# Trinamic.net
KiCad netlist of a schematic drawn in Altium Designer
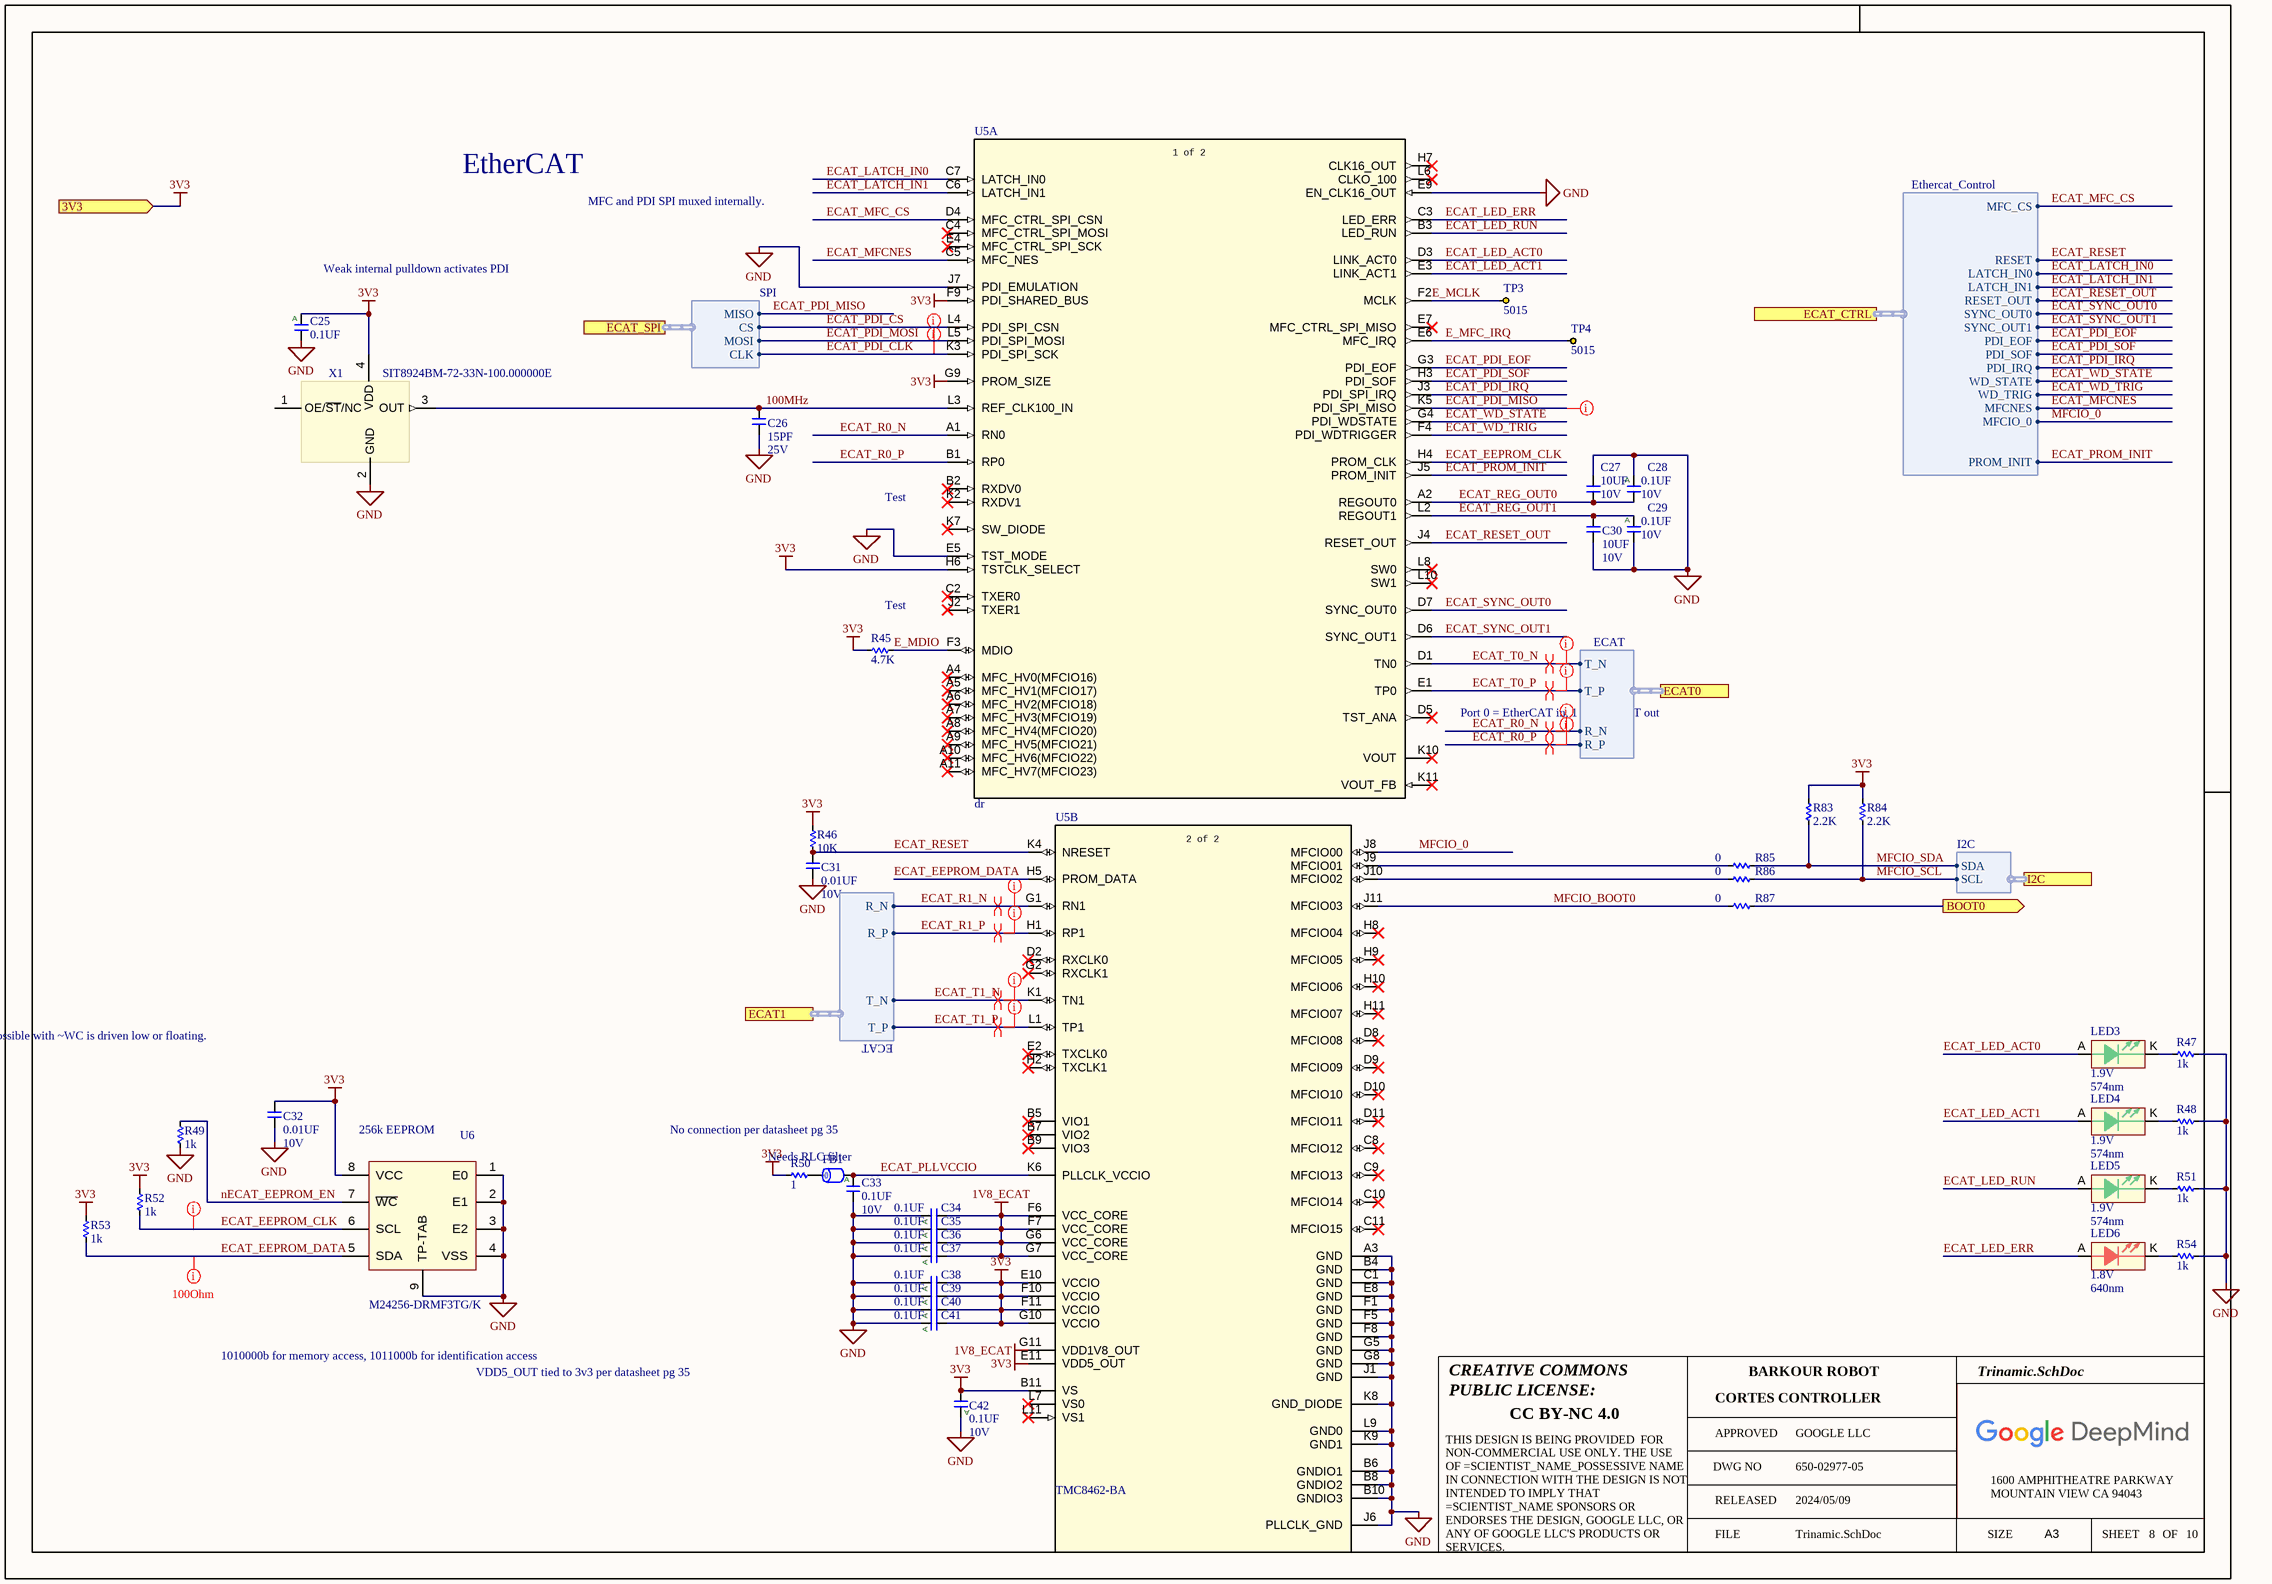
[diagram p0: Trinamic.SchDoc]

(export (version "E")
  (design (tool "Eeschema 10.0.6"))
  (components
    (comp (ref "C25")
      (value "0.1UF")
      (footprint "C0201Y")
      (description "CAP, CER, X6S, 0.1uF, 10V, 10%, 0201, AUTOGRADE")
      (fields (field (name "MFG") "MURATA") (field (name "VOLTAGE") "10V"))
      (libsource (lib "AltiumReleaseLibDB") (part "__Template_Cap_Auto"))
    )
    (comp (ref "C26")
      (value "15PF")
      (footprint "C0201")
      (description "CAP, CER, NP0, 15pF, 25V, 5%, 0201, 0.9mm T")
      (fields (field (name "MFG") "TDK") (field (name "VOLTAGE") "25V") (field (name "TOLERANCE") "5%"))
      (libsource (lib "AltiumReleaseLibDB") (part "__Template_Cap"))
    )
    (comp (ref "C27")
      (value "10UF")
      (footprint "C0402")
      (description "CAP, CER, X5R, 10uF, 10V, 20%, 0402, 0.7mm T")
      (fields (field (name "MFG") "SAMSUNG") (field (name "VOLTAGE") "10V") (field (name "TOLERANCE") "20%"))
      (libsource (lib "AltiumReleaseLibDB") (part "__Template_Cap"))
    )
    (comp (ref "C28")
      (value "0.1UF")
      (footprint "C0201Y")
      (description "CAP, CER, X6S, 0.1uF, 10V, 10%, 0201, AUTOGRADE")
      (fields (field (name "MFG") "MURATA") (field (name "VOLTAGE") "10V") (field (name "TOLERANCE") "10%"))
      (libsource (lib "AltiumReleaseLibDB") (part "__Template_Cap_Auto"))
    )
    (comp (ref "C29")
      (value "0.1UF")
      (footprint "C0201Y")
      (description "CAP, CER, X6S, 0.1uF, 10V, 10%, 0201, AUTOGRADE")
      (fields (field (name "MFG") "MURATA") (field (name "VOLTAGE") "10V") (field (name "TOLERANCE") "10%"))
      (libsource (lib "AltiumReleaseLibDB") (part "__Template_Cap_Auto"))
    )
    (comp (ref "C30")
      (value "10UF")
      (footprint "C0402")
      (description "CAP, CER, X5R, 10uF, 10V, 20%, 0402, 0.7mm T")
      (fields (field (name "MFG") "SAMSUNG") (field (name "VOLTAGE") "10V") (field (name "TOLERANCE") "20%"))
      (libsource (lib "AltiumReleaseLibDB") (part "__Template_Cap"))
    )
    (comp (ref "C31")
      (value "0.01UF")
      (footprint "C0201Y")
      (description "CAP, CER, X7R, 0.01uF, 10V, 10%, AUTO GRADE, 0201, 0.33mm T")
      (fields (field (name "MFG") "MURATA") (field (name "VOLTAGE") "10V") (field (name "TOLERANCE") "10%"))
      (libsource (lib "AltiumReleaseLibDB") (part "__Template_Cap"))
    )
    (comp (ref "C32")
      (value "0.01UF")
      (footprint "C0201Y")
      (description "CAP, CER, X7R, 0.01uF, 10V, 10%, AUTO GRADE, 0201, 0.33mm T")
      (fields (field (name "MFG") "MURATA") (field (name "VOLTAGE") "10V") (field (name "TOLERANCE") "10%"))
      (libsource (lib "AltiumReleaseLibDB") (part "__Template_Cap"))
    )
    (comp (ref "C33")
      (value "0.1UF")
      (footprint "C0201Y")
      (description "CAP, CER, X6S, 0.1uF, 10V, 10%, 0201, AUTOGRADE")
      (fields (field (name "MFG") "MURATA") (field (name "VOLTAGE") "10V") (field (name "TOLERANCE") "10%"))
      (libsource (lib "AltiumReleaseLibDB") (part "__Template_Cap_Auto"))
    )
    (comp (ref "C34")
      (value "0.1UF")
      (footprint "C0201Y")
      (description "CAP, CER, X6S, 0.1uF, 10V, 10%, 0201, AUTOGRADE")
      (fields (field (name "MFG") "MURATA") (field (name "VOLTAGE") "10V"))
      (libsource (lib "AltiumReleaseLibDB") (part "__Template_Cap_Auto"))
    )
    (comp (ref "C35")
      (value "0.1UF")
      (footprint "C0201Y")
      (description "CAP, CER, X6S, 0.1uF, 10V, 10%, 0201, AUTOGRADE")
      (fields (field (name "MFG") "MURATA") (field (name "VOLTAGE") "10V"))
      (libsource (lib "AltiumReleaseLibDB") (part "__Template_Cap_Auto"))
    )
    (comp (ref "C36")
      (value "0.1UF")
      (footprint "C0201Y")
      (description "CAP, CER, X6S, 0.1uF, 10V, 10%, 0201, AUTOGRADE")
      (fields (field (name "MFG") "MURATA") (field (name "VOLTAGE") "10V"))
      (libsource (lib "AltiumReleaseLibDB") (part "__Template_Cap_Auto"))
    )
    (comp (ref "C37")
      (value "0.1UF")
      (footprint "C0201Y")
      (description "CAP, CER, X6S, 0.1uF, 10V, 10%, 0201, AUTOGRADE")
      (fields (field (name "MFG") "MURATA") (field (name "VOLTAGE") "10V"))
      (libsource (lib "AltiumReleaseLibDB") (part "__Template_Cap_Auto"))
    )
    (comp (ref "C38")
      (value "0.1UF")
      (footprint "C0201Y")
      (description "CAP, CER, X6S, 0.1uF, 10V, 10%, 0201, AUTOGRADE")
      (fields (field (name "MFG") "MURATA") (field (name "VOLTAGE") "10V"))
      (libsource (lib "AltiumReleaseLibDB") (part "__Template_Cap_Auto"))
    )
    (comp (ref "C39")
      (value "0.1UF")
      (footprint "C0201Y")
      (description "CAP, CER, X6S, 0.1uF, 10V, 10%, 0201, AUTOGRADE")
      (fields (field (name "MFG") "MURATA") (field (name "VOLTAGE") "10V"))
      (libsource (lib "AltiumReleaseLibDB") (part "__Template_Cap_Auto"))
    )
    (comp (ref "C40")
      (value "0.1UF")
      (footprint "C0201Y")
      (description "CAP, CER, X6S, 0.1uF, 10V, 10%, 0201, AUTOGRADE")
      (fields (field (name "MFG") "MURATA") (field (name "VOLTAGE") "10V"))
      (libsource (lib "AltiumReleaseLibDB") (part "__Template_Cap_Auto"))
    )
    (comp (ref "C41")
      (value "0.1UF")
      (footprint "C0201Y")
      (description "CAP, CER, X6S, 0.1uF, 10V, 10%, 0201, AUTOGRADE")
      (fields (field (name "MFG") "MURATA") (field (name "VOLTAGE") "10V"))
      (libsource (lib "AltiumReleaseLibDB") (part "__Template_Cap_Auto"))
    )
    (comp (ref "C42")
      (value "0.1UF")
      (footprint "C0201Y")
      (description "CAP, CER, X6S, 0.1uF, 10V, 10%, 0201, AUTOGRADE")
      (fields (field (name "MFG") "MURATA") (field (name "VOLTAGE") "10V") (field (name "TOLERANCE") "10%"))
      (libsource (lib "AltiumReleaseLibDB") (part "__Template_Cap_Auto"))
    )
    (comp (ref "FB1")
      (value "__Template_Ferrite_Bead")
      (footprint "L0201_H0.33MM")
      (description "FERRITE, BEAD, 600OHMS @100MHZ, 25%, 250mA, 900 mOHM DCR, 0201")
      (fields (field (name "MFG") "Murata Electronics North America"))
      (libsource (lib "AltiumReleaseLibDB") (part "__Template_Ferrite_Bead"))
    )
    (comp (ref "LED3")
      (value "__Template_LED_GREEN_AK")
      (footprint "LED_APHHS1005LCGCK")
      (description "LED, GREEN, 574nm, 2mA, CLEAR, 0402")
      (fields
        (field (name "MFG") "Kingbright")
        (field (name "VOLTAGE – FORWARD (VF) (MAX) @ IF") "1.9V")
        (field (name "COLOR / WAVELENGTH") "574nm")
      )
      (libsource (lib "AltiumReleaseLibDB") (part "__Template_LED_GREEN_AK"))
    )
    (comp (ref "LED4")
      (value "__Template_LED_GREEN_AK")
      (footprint "LED_APHHS1005LCGCK")
      (description "LED, GREEN, 574nm, 2mA, CLEAR, 0402")
      (fields
        (field (name "MFG") "Kingbright")
        (field (name "VOLTAGE – FORWARD (VF) (MAX) @ IF") "1.9V")
        (field (name "COLOR / WAVELENGTH") "574nm")
      )
      (libsource (lib "AltiumReleaseLibDB") (part "__Template_LED_GREEN_AK"))
    )
    (comp (ref "LED5")
      (value "__Template_LED_GREEN_AK")
      (footprint "LED_APHHS1005LCGCK")
      (description "LED, GREEN, 574nm, 2mA, CLEAR, 0402")
      (fields
        (field (name "MFG") "Kingbright")
        (field (name "VOLTAGE – FORWARD (VF) (MAX) @ IF") "1.9V")
        (field (name "COLOR / WAVELENGTH") "574nm")
      )
      (libsource (lib "AltiumReleaseLibDB") (part "__Template_LED_GREEN_AK"))
    )
    (comp (ref "LED6")
      (value "__Template_LED_RED_AK")
      (footprint "LED_APHHS1005LCGCK")
      (description "LED, RED, 640NM, 2mA, CLEAR, 0402")
      (fields
        (field (name "MFG") "Kingbright")
        (field (name "VOLTAGE – FORWARD (VF) (MAX) @ IF") "1.8V")
        (field (name "COLOR / WAVELENGTH") "640nm")
      )
      (libsource (lib "AltiumReleaseLibDB") (part "__Template_LED_RED_AK"))
    )
    (comp (ref "R45")
      (value "4.7K")
      (footprint "R0201_H0.26MM")
      (description "RES, 4.7K, 1%, 1/20W, 0201, AUTOGRADE")
      (fields (field (name "MFG") "Panasonic Electronic Components") (field (name "POWER") "0.05W, 1/20W"))
      (libsource (lib "AltiumReleaseLibDB") (part "__Template_Resistor"))
    )
    (comp (ref "R46")
      (value "10K")
      (footprint "R0201_H0.26MM")
      (description "RES, 10K, 1%, 1/20W, 0201, AUTOGRADE")
      (fields (field (name "MFG") "PANASONIC") (field (name "POWER") "1/20W"))
      (libsource (lib "AltiumReleaseLibDB") (part "__Template_Resistor"))
    )
    (comp (ref "R47")
      (value "1k")
      (footprint "R0201_H0.26MM")
      (description "RES, 1K, 1%, 1/20W, 0201, AUTOGRADE")
      (fields (field (name "MFG") "Bourns Inc.") (field (name "POWER") "0.05W, 1/20W"))
      (libsource (lib "AltiumReleaseLibDB") (part "__Template_Resistor"))
    )
    (comp (ref "R48")
      (value "1k")
      (footprint "R0201_H0.26MM")
      (description "RES, 1K, 1%, 1/20W, 0201, AUTOGRADE")
      (fields (field (name "MFG") "Bourns Inc.") (field (name "POWER") "0.05W, 1/20W"))
      (libsource (lib "AltiumReleaseLibDB") (part "__Template_Resistor"))
    )
    (comp (ref "R49")
      (value "1k")
      (footprint "R0201_H0.26MM")
      (description "RES, 1K, 1%, 1/20W, 0201, AUTOGRADE")
      (fields (field (name "MFG") "Bourns Inc.") (field (name "POWER") "0.05W, 1/20W"))
      (libsource (lib "AltiumReleaseLibDB") (part "__Template_Resistor"))
    )
    (comp (ref "R50")
      (value "1")
      (footprint "R0201")
      (description "RES, 1.0, 5%, 1/20W, 0201")
      (fields (field (name "MFG") "PANASONIC") (field (name "POWER") "1/20W"))
      (libsource (lib "AltiumReleaseLibDB") (part "__Template_Resistor"))
    )
    (comp (ref "R51")
      (value "1k")
      (footprint "R0201_H0.26MM")
      (description "RES, 1K, 1%, 1/20W, 0201, AUTOGRADE")
      (fields (field (name "MFG") "Bourns Inc.") (field (name "POWER") "0.05W, 1/20W"))
      (libsource (lib "AltiumReleaseLibDB") (part "__Template_Resistor"))
    )
    (comp (ref "R52")
      (value "1k")
      (footprint "R0201_H0.26MM")
      (description "RES, 1K, 1%, 1/20W, 0201, AUTOGRADE")
      (fields (field (name "MFG") "Bourns Inc.") (field (name "POWER") "0.05W, 1/20W"))
      (libsource (lib "AltiumReleaseLibDB") (part "__Template_Resistor"))
    )
    (comp (ref "R53")
      (value "1k")
      (footprint "R0201_H0.26MM")
      (description "RES, 1K, 1%, 1/20W, 0201, AUTOGRADE")
      (fields (field (name "MFG") "Bourns Inc.") (field (name "POWER") "0.05W, 1/20W"))
      (libsource (lib "AltiumReleaseLibDB") (part "__Template_Resistor"))
    )
    (comp (ref "R54")
      (value "1k")
      (footprint "R0201_H0.26MM")
      (description "RES, 1K, 1%, 1/20W, 0201, AUTOGRADE")
      (fields (field (name "MFG") "Bourns Inc.") (field (name "POWER") "0.05W, 1/20W"))
      (libsource (lib "AltiumReleaseLibDB") (part "__Template_Resistor"))
    )
    (comp (ref "R83")
      (value "2.2K")
      (footprint "R0201")
      (description "Resistor, 2.20K Ohms, 0201, 0.05W, ±1%")
      (fields (field (name "MFG") "PANASONIC") (field (name "POWER") "1/20W"))
      (libsource (lib "AltiumReleaseLibDB") (part "__Template_Resistor"))
    )
    (comp (ref "R84")
      (value "2.2K")
      (footprint "R0201")
      (description "Resistor, 2.20K Ohms, 0201, 0.05W, ±1%")
      (fields (field (name "MFG") "PANASONIC") (field (name "POWER") "1/20W"))
      (libsource (lib "AltiumReleaseLibDB") (part "__Template_Resistor"))
    )
    (comp (ref "R85")
      (value "0")
      (footprint "R0402")
      (description "RES, 0, JUMPER, 1/16W, 0402")
      (fields (field (name "MFG") "YAGEO") (field (name "POWER") "1/16W"))
      (libsource (lib "AltiumReleaseLibDB") (part "__Template_Resistor"))
    )
    (comp (ref "R86")
      (value "0")
      (footprint "R0402")
      (description "RES, 0, JUMPER, 1/16W, 0402")
      (fields (field (name "MFG") "YAGEO") (field (name "POWER") "1/16W"))
      (libsource (lib "AltiumReleaseLibDB") (part "__Template_Resistor"))
    )
    (comp (ref "R87")
      (value "0")
      (footprint "R0402")
      (description "RES, 0, JUMPER, 1/16W, 0402")
      (fields (field (name "MFG") "YAGEO") (field (name "POWER") "1/16W"))
      (libsource (lib "AltiumReleaseLibDB") (part "__Template_Resistor"))
    )
    (comp (ref "TP3")
      (value "KEYSTONE5015_NOSILK")
      (footprint "KEYSTONE_5015_NS")
      (description "HW, TEST POINT, NO SILKSCREEN, PC MINIATURE, 0.25mm T, 1.52mm HEIGHT, SILVER PLATING, SMT")
      (fields (field (name "MFG") "Keystone Electronics Corp.") (field (name "MFG P/N") "5015"))
      (libsource (lib "AltiumReleaseLibDB") (part "TEST_KEYSTONE5015_NOSILK"))
    )
    (comp (ref "TP4")
      (value "KEYSTONE5015_NOSILK")
      (footprint "KEYSTONE_5015_NS")
      (description "HW, TEST POINT, NO SILKSCREEN, PC MINIATURE, 0.25mm T, 1.52mm HEIGHT, SILVER PLATING, SMT")
      (fields (field (name "MFG") "Keystone Electronics Corp.") (field (name "MFG P/N") "5015"))
      (libsource (lib "AltiumReleaseLibDB") (part "TEST_KEYSTONE5015_NOSILK"))
    )
    (comp (ref "U5")
      (value "PROCESSOR_TRINAMIC_TMC8462-BA")
      (footprint "BGA121C75P11X11_900X900X145")
      (description "IC, CONTROLLER, TMC8462, ETHERNET, 100Mb, SPI, PWM O/P, 100mA, BGA-121")
      (fields (field (name "MFG") "Trinamic Motion Control GmbH") (field (name "MFG P/N") "dr"))
      (libsource (lib "AltiumReleaseLibDB") (part "PROCESSOR_TRINAMIC_TMC8462-BA"))
    )
    (comp (ref "U6")
      (value "EEPROM_M24256-DRMF3TG/K")
      (footprint "8WFDFN300X200X80-8-TP")
      (description "IC, MEMORY, M24256, EEPROM, 256Kb, I2C, 1MHz, MLP-8, AUTOGRADE")
      (fields (field (name "MFG") "STMicroelectronics") (field (name "MFG P/N") "M24256-DRMF3TG/K"))
      (libsource (lib "AltiumReleaseLibDB") (part "EEPROM_M24256-DRMF3TG/K"))
    )
    (comp (ref "X1")
      (value "XTAL_SIT8924BM-72-33N-100.000000")
      (footprint "XTAL_SIT8924BM-72-33N-100.000000")
      (description "OSC, MEMS, XO, 100MHZ, +/-25PPM STAB, LVCMOS, 3.3V, SMD-4, AUTOGRADE")
      (fields (field (name "MFG") "SiTIME") (field (name "MFG P/N") "SIT8924BM-72-33N-100.000000E"))
      (libsource (lib "AltiumReleaseLibDB") (part "XTAL_SIT8924BM-72-33N-100.000000"))
    )
  )
  (nets
    (net (code "5") (name "/100MHz") (class "Default")
      (node (ref "C26") (pin "1") (pintype "passive"))
      (node (ref "U5") (pin "L3") (pinfunction "REF_CLK100_IN_L3") (pintype "input"))
      (node (ref "X1") (pin "3") (pinfunction "OUT_3") (pintype "output"))
    )
    (net (code "6") (name "/BOOT0") (class "Default") (node (ref "R87") (pin "2") (pintype "passive")))
    (net (code "7") (name "/ECAT_EEPROM_CLK") (class "Default")
      (node (ref "R52") (pin "1") (pintype "passive"))
      (node (ref "U5") (pin "H4") (pinfunction "PROM_CLK_H4") (pintype "output"))
      (node (ref "U6") (pin "6") (pinfunction "SCL_6") (pintype "passive"))
    )
    (net (code "8") (name "/ECAT_EEPROM_DATA") (class "Default")
      (node (ref "R53") (pin "1") (pintype "passive"))
      (node (ref "U5") (pin "H5") (pinfunction "PROM_DATA_H5") (pintype "bidirectional"))
      (node (ref "U6") (pin "5") (pinfunction "SDA_5") (pintype "passive"))
    )
    (net (code "9") (name "/ECAT_LATCH_IN0") (class "Default")
      (node (ref "U5") (pin "C7") (pinfunction "LATCH_IN0_C7") (pintype "input"))
    )
    (net (code "10") (name "/ECAT_LATCH_IN1") (class "Default")
      (node (ref "U5") (pin "C6") (pinfunction "LATCH_IN1_C6") (pintype "input"))
    )
    (net (code "11") (name "/ECAT_LED_ACT0") (class "Default")
      (node (ref "LED3") (pin "A") (pinfunction "A_A") (pintype "passive"))
      (node (ref "U5") (pin "D3") (pinfunction "LINK_ACT0_D3") (pintype "output"))
    )
    (net (code "12") (name "/ECAT_LED_ACT1") (class "Default")
      (node (ref "LED4") (pin "A") (pinfunction "A_A") (pintype "passive"))
      (node (ref "U5") (pin "E3") (pinfunction "LINK_ACT1_E3") (pintype "output"))
    )
    (net (code "13") (name "/ECAT_LED_ERR") (class "Default")
      (node (ref "LED6") (pin "A") (pinfunction "A_A") (pintype "passive"))
      (node (ref "U5") (pin "C3") (pinfunction "LED_ERR_C3") (pintype "output"))
    )
    (net (code "14") (name "/ECAT_LED_RUN") (class "Default")
      (node (ref "LED5") (pin "A") (pinfunction "A_A") (pintype "passive"))
      (node (ref "U5") (pin "B3") (pinfunction "LED_RUN_B3") (pintype "output"))
    )
    (net (code "15") (name "/ECAT_MFCNES") (class "Default")
      (node (ref "U5") (pin "C5") (pinfunction "MFC_NES_C5") (pintype "input"))
    )
    (net (code "16") (name "/ECAT_MFC_CS") (class "Default")
      (node (ref "U5") (pin "D4") (pinfunction "MFC_CTRL_SPI_CSN_D4") (pintype "input"))
    )
    (net (code "17") (name "/ECAT_PDI_CLK") (class "Default")
      (node (ref "U5") (pin "K3") (pinfunction "PDI_SPI_SCK_K3") (pintype "input"))
    )
    (net (code "18") (name "/ECAT_PDI_CS") (class "Default")
      (node (ref "U5") (pin "L4") (pinfunction "PDI_SPI_CSN_L4") (pintype "input"))
    )
    (net (code "19") (name "/ECAT_PDI_EOF") (class "Default")
      (node (ref "U5") (pin "G3") (pinfunction "PDI_EOF_G3") (pintype "output"))
    )
    (net (code "20") (name "/ECAT_PDI_IRQ") (class "Default")
      (node (ref "U5") (pin "J3") (pinfunction "PDI_SPI_IRQ_J3") (pintype "output"))
    )
    (net (code "21") (name "/ECAT_PDI_MISO") (class "Default")
      (node (ref "U5") (pin "K5") (pinfunction "PDI_SPI_MISO_K5") (pintype "output"))
    )
    (net (code "22") (name "/ECAT_PDI_MOSI") (class "Default")
      (node (ref "U5") (pin "L5") (pinfunction "PDI_SPI_MOSI_L5") (pintype "input"))
    )
    (net (code "23") (name "/ECAT_PDI_SOF") (class "Default")
      (node (ref "U5") (pin "H3") (pinfunction "PDI_SOF_H3") (pintype "output"))
    )
    (net (code "24") (name "/ECAT_PLLVCCIO") (class "Default")
      (node (ref "C33") (pin "1") (pintype "passive"))
      (node (ref "FB1") (pin "2") (pinfunction "2_2") (pintype "passive"))
      (node (ref "U5") (pin "K6") (pinfunction "PLLCLK_VCCIO_K6") (pintype "power_in"))
    )
    (net (code "25") (name "/ECAT_PROM_INIT") (class "Default")
      (node (ref "U5") (pin "J5") (pinfunction "PROM_INIT_J5") (pintype "output"))
    )
    (net (code "26") (name "/ECAT_R0_N") (class "Default")
      (node (ref "U5") (pin "A1") (pinfunction "RN0_A1") (pintype "input"))
    )
    (net (code "27") (name "/ECAT_R0_P") (class "Default")
      (node (ref "U5") (pin "B1") (pinfunction "RP0_B1") (pintype "input"))
    )
    (net (code "28") (name "/ECAT_R1_N") (class "Default")
      (node (ref "U5") (pin "G1") (pinfunction "RN1_G1") (pintype "bidirectional"))
    )
    (net (code "29") (name "/ECAT_R1_P") (class "Default")
      (node (ref "U5") (pin "H1") (pinfunction "RP1_H1") (pintype "bidirectional"))
    )
    (net (code "30") (name "/ECAT_REG_OUT0") (class "Default")
      (node (ref "C27") (pin "2") (pintype "passive"))
      (node (ref "C28") (pin "2") (pintype "passive"))
      (node (ref "U5") (pin "A2") (pinfunction "REGOUT0_A2") (pintype "output"))
    )
    (net (code "31") (name "/ECAT_REG_OUT1") (class "Default")
      (node (ref "C29") (pin "1") (pintype "passive"))
      (node (ref "C30") (pin "1") (pintype "passive"))
      (node (ref "U5") (pin "L2") (pinfunction "REGOUT1_L2") (pintype "output"))
    )
    (net (code "32") (name "/ECAT_RESET") (class "Default")
      (node (ref "C31") (pin "1") (pintype "passive"))
      (node (ref "R46") (pin "1") (pintype "passive"))
      (node (ref "U5") (pin "K4") (pinfunction "NRESET_K4") (pintype "bidirectional"))
    )
    (net (code "33") (name "/ECAT_RESET_OUT") (class "Default")
      (node (ref "U5") (pin "J4") (pinfunction "RESET_OUT_J4") (pintype "output"))
    )
    (net (code "34") (name "/ECAT_SYNC_OUT0") (class "Default")
      (node (ref "U5") (pin "D7") (pinfunction "SYNC_OUT0_D7") (pintype "output"))
    )
    (net (code "35") (name "/ECAT_SYNC_OUT1") (class "Default")
      (node (ref "U5") (pin "D6") (pinfunction "SYNC_OUT1_D6") (pintype "output"))
    )
    (net (code "36") (name "/ECAT_T0_N") (class "Default")
      (node (ref "U5") (pin "D1") (pinfunction "TN0_D1") (pintype "output"))
    )
    (net (code "37") (name "/ECAT_T0_P") (class "Default")
      (node (ref "U5") (pin "E1") (pinfunction "TP0_E1") (pintype "output"))
    )
    (net (code "38") (name "/ECAT_T1_N") (class "Default")
      (node (ref "U5") (pin "K1") (pinfunction "TN1_K1") (pintype "bidirectional"))
    )
    (net (code "39") (name "/ECAT_T1_P") (class "Default")
      (node (ref "U5") (pin "L1") (pinfunction "TP1_L1") (pintype "bidirectional"))
    )
    (net (code "40") (name "/ECAT_WD_STATE") (class "Default")
      (node (ref "U5") (pin "G4") (pinfunction "PDI_WDSTATE_G4") (pintype "output"))
    )
    (net (code "41") (name "/ECAT_WD_TRIG") (class "Default")
      (node (ref "U5") (pin "F4") (pinfunction "PDI_WDTRIGGER_F4") (pintype "output"))
    )
    (net (code "42") (name "/E_MCLK") (class "Default")
      (node (ref "TP3") (pin "1") (pintype "passive"))
      (node (ref "U5") (pin "F2") (pinfunction "MCLK_F2") (pintype "output"))
    )
    (net (code "43") (name "/E_MDIO") (class "Default")
      (node (ref "R45") (pin "1") (pintype "passive"))
      (node (ref "U5") (pin "F3") (pinfunction "MDIO_F3") (pintype "bidirectional"))
    )
    (net (code "44") (name "/E_MFC_IRQ") (class "Default")
      (node (ref "TP4") (pin "1") (pintype "passive"))
      (node (ref "U5") (pin "E6") (pinfunction "MFC_IRQ_E6") (pintype "output"))
    )
    (net (code "45") (name "/MFCIO_0") (class "Default")
      (node (ref "U5") (pin "J8") (pinfunction "MFCIO00_J8") (pintype "bidirectional"))
    )
    (net (code "46") (name "/MFCIO_BOOT0") (class "Default")
      (node (ref "R87") (pin "1") (pintype "passive"))
      (node (ref "U5") (pin "J11") (pinfunction "MFCIO03_J11") (pintype "bidirectional"))
    )
    (net (code "47") (name "/MFCIO_SCL") (class "Default")
      (node (ref "R84") (pin "1") (pintype "passive"))
      (node (ref "R86") (pin "2") (pintype "passive"))
    )
    (net (code "48") (name "/MFCIO_SDA") (class "Default")
      (node (ref "R83") (pin "1") (pintype "passive"))
      (node (ref "R85") (pin "2") (pintype "passive"))
    )
    (net (code "49") (name "/nECAT_EEPROM_EN") (class "Default")
      (node (ref "R49") (pin "2") (pintype "passive"))
      (node (ref "U6") (pin "7") (pinfunction "~{WC}_7") (pintype "passive"))
    )
    (net (code "54") (name "1V8_ECAT") (class "Default")
      (node (ref "C34") (pin "2") (pintype "passive"))
      (node (ref "C35") (pin "2") (pintype "passive"))
      (node (ref "C36") (pin "2") (pintype "passive"))
      (node (ref "C37") (pin "2") (pintype "passive"))
      (node (ref "U5") (pin "F6") (pinfunction "VCC_CORE_F6") (pintype "power_in"))
      (node (ref "U5") (pin "F7") (pinfunction "VCC_CORE_F7") (pintype "power_in"))
      (node (ref "U5") (pin "G11") (pinfunction "VDD1V8_OUT_G11") (pintype "power_in"))
      (node (ref "U5") (pin "G6") (pinfunction "VCC_CORE_G6") (pintype "power_in"))
      (node (ref "U5") (pin "G7") (pinfunction "VCC_CORE_G7") (pintype "power_in"))
    )
    (net (code "55") (name "3V3") (class "Default")
      (node (ref "C25") (pin "1") (pintype "passive"))
      (node (ref "C32") (pin "1") (pintype "passive"))
      (node (ref "C38") (pin "2") (pintype "passive"))
      (node (ref "C39") (pin "2") (pintype "passive"))
      (node (ref "C40") (pin "2") (pintype "passive"))
      (node (ref "C41") (pin "2") (pintype "passive"))
      (node (ref "C42") (pin "2") (pintype "passive"))
      (node (ref "R45") (pin "2") (pintype "passive"))
      (node (ref "R46") (pin "2") (pintype "passive"))
      (node (ref "R50") (pin "1") (pintype "passive"))
      (node (ref "R52") (pin "2") (pintype "passive"))
      (node (ref "R53") (pin "2") (pintype "passive"))
      (node (ref "R83") (pin "2") (pintype "passive"))
      (node (ref "R84") (pin "2") (pintype "passive"))
      (node (ref "U5") (pin "B11") (pinfunction "VS_B11") (pintype "power_in"))
      (node (ref "U5") (pin "E10") (pinfunction "VCCIO_E10") (pintype "power_in"))
      (node (ref "U5") (pin "E11") (pinfunction "VDD5_OUT_E11") (pintype "power_in"))
      (node (ref "U5") (pin "F10") (pinfunction "VCCIO_F10") (pintype "power_in"))
      (node (ref "U5") (pin "F11") (pinfunction "VCCIO_F11") (pintype "power_in"))
      (node (ref "U5") (pin "F9") (pinfunction "PDI_SHARED_BUS_F9") (pintype "input"))
      (node (ref "U5") (pin "G10") (pinfunction "VCCIO_G10") (pintype "power_in"))
      (node (ref "U5") (pin "G9") (pinfunction "PROM_SIZE_G9") (pintype "input"))
      (node (ref "U5") (pin "H6") (pinfunction "TSTCLK_SELECT_H6") (pintype "input"))
      (node (ref "U6") (pin "8") (pinfunction "VCC_8") (pintype "passive"))
      (node (ref "X1") (pin "4") (pinfunction "VDD_4") (pintype "power_in"))
    )
    (net (code "56") (name "GND") (class "Default")
      (node (ref "C25") (pin "2") (pintype "passive"))
      (node (ref "C26") (pin "2") (pintype "passive"))
      (node (ref "C27") (pin "1") (pintype "passive"))
      (node (ref "C28") (pin "1") (pintype "passive"))
      (node (ref "C29") (pin "2") (pintype "passive"))
      (node (ref "C30") (pin "2") (pintype "passive"))
      (node (ref "C31") (pin "2") (pintype "passive"))
      (node (ref "C32") (pin "2") (pintype "passive"))
      (node (ref "C33") (pin "2") (pintype "passive"))
      (node (ref "C34") (pin "1") (pintype "passive"))
      (node (ref "C35") (pin "1") (pintype "passive"))
      (node (ref "C36") (pin "1") (pintype "passive"))
      (node (ref "C37") (pin "1") (pintype "passive"))
      (node (ref "C38") (pin "1") (pintype "passive"))
      (node (ref "C39") (pin "1") (pintype "passive"))
      (node (ref "C40") (pin "1") (pintype "passive"))
      (node (ref "C41") (pin "1") (pintype "passive"))
      (node (ref "C42") (pin "1") (pintype "passive"))
      (node (ref "R47") (pin "1") (pintype "passive"))
      (node (ref "R48") (pin "1") (pintype "passive"))
      (node (ref "R49") (pin "1") (pintype "passive"))
      (node (ref "R51") (pin "1") (pintype "passive"))
      (node (ref "R54") (pin "1") (pintype "passive"))
      (node (ref "U5") (pin "A3") (pinfunction "GND_A3") (pintype "power_in"))
      (node (ref "U5") (pin "B10") (pinfunction "GNDIO3_B10") (pintype "power_in"))
      (node (ref "U5") (pin "B4") (pinfunction "GND_B4") (pintype "power_in"))
      (node (ref "U5") (pin "B6") (pinfunction "GNDIO1_B6") (pintype "power_in"))
      (node (ref "U5") (pin "B8") (pinfunction "GNDIO2_B8") (pintype "power_in"))
      (node (ref "U5") (pin "C1") (pinfunction "GND_C1") (pintype "power_in"))
      (node (ref "U5") (pin "E5") (pinfunction "TST_MODE_E5") (pintype "input"))
      (node (ref "U5") (pin "E8") (pinfunction "GND_E8") (pintype "power_in"))
      (node (ref "U5") (pin "E9") (pinfunction "EN_CLK16_OUT_E9") (pintype "input"))
      (node (ref "U5") (pin "F1") (pinfunction "GND_F1") (pintype "power_in"))
      (node (ref "U5") (pin "F5") (pinfunction "GND_F5") (pintype "power_in"))
      (node (ref "U5") (pin "F8") (pinfunction "GND_F8") (pintype "power_in"))
      (node (ref "U5") (pin "G5") (pinfunction "GND_G5") (pintype "power_in"))
      (node (ref "U5") (pin "G8") (pinfunction "GND_G8") (pintype "power_in"))
      (node (ref "U5") (pin "J1") (pinfunction "GND_J1") (pintype "power_in"))
      (node (ref "U5") (pin "J6") (pinfunction "PLLCLK_GND_J6") (pintype "power_in"))
      (node (ref "U5") (pin "J7") (pinfunction "PDI_EMULATION_J7") (pintype "input"))
      (node (ref "U5") (pin "K8") (pinfunction "GND_DIODE_K8") (pintype "power_in"))
      (node (ref "U5") (pin "K9") (pinfunction "GND1_K9") (pintype "power_in"))
      (node (ref "U5") (pin "L9") (pinfunction "GND0_L9") (pintype "power_in"))
      (node (ref "U6") (pin "1") (pinfunction "E0_1") (pintype "passive"))
      (node (ref "U6") (pin "2") (pinfunction "E1_2") (pintype "passive"))
      (node (ref "U6") (pin "3") (pinfunction "E2_3") (pintype "passive"))
      (node (ref "U6") (pin "4") (pinfunction "VSS_4") (pintype "passive"))
      (node (ref "U6") (pin "9") (pinfunction "TP-TAB_9") (pintype "power_in"))
      (node (ref "X1") (pin "2") (pinfunction "GND_2") (pintype "power_in"))
    )
    (net (code "57") (name "Net-(FB1-Pad1)") (class "Default")
      (node (ref "FB1") (pin "1") (pinfunction "1_1") (pintype "passive"))
      (node (ref "R50") (pin "2") (pintype "passive"))
    )
    (net (code "58") (name "Net-(LED3-PadK)") (class "Default")
      (node (ref "LED3") (pin "K") (pinfunction "K_K") (pintype "passive"))
      (node (ref "R47") (pin "2") (pintype "passive"))
    )
    (net (code "59") (name "Net-(LED4-PadK)") (class "Default")
      (node (ref "LED4") (pin "K") (pinfunction "K_K") (pintype "passive"))
      (node (ref "R48") (pin "2") (pintype "passive"))
    )
    (net (code "60") (name "Net-(LED5-PadK)") (class "Default")
      (node (ref "LED5") (pin "K") (pinfunction "K_K") (pintype "passive"))
      (node (ref "R51") (pin "2") (pintype "passive"))
    )
    (net (code "61") (name "Net-(LED6-PadK)") (class "Default")
      (node (ref "LED6") (pin "K") (pinfunction "K_K") (pintype "passive"))
      (node (ref "R54") (pin "2") (pintype "passive"))
    )
    (net (code "62") (name "Net-(U5B-MFCIO01)") (class "Default")
      (node (ref "R85") (pin "1") (pintype "passive"))
      (node (ref "U5") (pin "J9") (pinfunction "MFCIO01_J9") (pintype "bidirectional"))
    )
    (net (code "63") (name "Net-(U5B-MFCIO02)") (class "Default")
      (node (ref "R86") (pin "1") (pintype "passive"))
      (node (ref "U5") (pin "J10") (pinfunction "MFCIO02_J10") (pintype "bidirectional"))
    )
    (net (code "64") (name "unconnected-(U5A-CLK16_OUT-PadH7)") (class "Default")
      (node (ref "U5") (pin "H7") (pinfunction "CLK16_OUT_H7") (pintype "output+no_connect"))
    )
    (net (code "65") (name "unconnected-(U5A-CLKO_100-PadL6)") (class "Default")
      (node (ref "U5") (pin "L6") (pinfunction "CLKO_100_L6") (pintype "output+no_connect"))
    )
    (net (code "66") (name "unconnected-(U5A-MFC_CTRL_SPI_MISO-PadE7)") (class "Default")
      (node (ref "U5") (pin "E7") (pinfunction "MFC_CTRL_SPI_MISO_E7") (pintype "output+no_connect"))
    )
    (net (code "67") (name "unconnected-(U5A-MFC_CTRL_SPI_MOSI-PadC4)") (class "Default")
      (node (ref "U5") (pin "C4") (pinfunction "MFC_CTRL_SPI_MOSI_C4") (pintype "input+no_connect"))
    )
    (net (code "68") (name "unconnected-(U5A-MFC_CTRL_SPI_SCK-PadE4)") (class "Default")
      (node (ref "U5") (pin "E4") (pinfunction "MFC_CTRL_SPI_SCK_E4") (pintype "input+no_connect"))
    )
    (net (code "69") (name "unconnected-(U5A-MFC_HV0(MFCIO16)-PadA4)") (class "Default")
      (node (ref "U5") (pin "A4") (pinfunction "MFC_HV0(MFCIO16)_A4") (pintype "bidirectional+no_connect"))
    )
    (net (code "70") (name "unconnected-(U5A-MFC_HV1(MFCIO17)-PadA5)") (class "Default")
      (node (ref "U5") (pin "A5") (pinfunction "MFC_HV1(MFCIO17)_A5") (pintype "bidirectional+no_connect"))
    )
    (net (code "71") (name "unconnected-(U5A-MFC_HV2(MFCIO18)-PadA6)") (class "Default")
      (node (ref "U5") (pin "A6") (pinfunction "MFC_HV2(MFCIO18)_A6") (pintype "bidirectional+no_connect"))
    )
    (net (code "72") (name "unconnected-(U5A-MFC_HV3(MFCIO19)-PadA7)") (class "Default")
      (node (ref "U5") (pin "A7") (pinfunction "MFC_HV3(MFCIO19)_A7") (pintype "bidirectional+no_connect"))
    )
    (net (code "73") (name "unconnected-(U5A-MFC_HV4(MFCIO20)-PadA8)") (class "Default")
      (node (ref "U5") (pin "A8") (pinfunction "MFC_HV4(MFCIO20)_A8") (pintype "bidirectional+no_connect"))
    )
    (net (code "74") (name "unconnected-(U5A-MFC_HV5(MFCIO21)-PadA9)") (class "Default")
      (node (ref "U5") (pin "A9") (pinfunction "MFC_HV5(MFCIO21)_A9") (pintype "bidirectional+no_connect"))
    )
    (net (code "75") (name "unconnected-(U5A-MFC_HV6(MFCIO22)-PadA10)") (class "Default")
      (node (ref "U5") (pin "A10") (pinfunction "MFC_HV6(MFCIO22)_A10") (pintype "bidirectional+no_connect"))
    )
    (net (code "76") (name "unconnected-(U5A-MFC_HV7(MFCIO23)-PadA11)") (class "Default")
      (node (ref "U5") (pin "A11") (pinfunction "MFC_HV7(MFCIO23)_A11") (pintype "bidirectional+no_connect"))
    )
    (net (code "77") (name "unconnected-(U5A-RXDV0-PadB2)") (class "Default")
      (node (ref "U5") (pin "B2") (pinfunction "RXDV0_B2") (pintype "input+no_connect"))
    )
    (net (code "78") (name "unconnected-(U5A-RXDV1-PadK2)") (class "Default")
      (node (ref "U5") (pin "K2") (pinfunction "RXDV1_K2") (pintype "input+no_connect"))
    )
    (net (code "79") (name "unconnected-(U5A-SW0-PadL8)") (class "Default")
      (node (ref "U5") (pin "L8") (pinfunction "SW0_L8") (pintype "output+no_connect"))
    )
    (net (code "80") (name "unconnected-(U5A-SW1-PadL10)") (class "Default")
      (node (ref "U5") (pin "L10") (pinfunction "SW1_L10") (pintype "output+no_connect"))
    )
    (net (code "81") (name "unconnected-(U5A-SW_DIODE-PadK7)") (class "Default")
      (node (ref "U5") (pin "K7") (pinfunction "SW_DIODE_K7") (pintype "input+no_connect"))
    )
    (net (code "82") (name "unconnected-(U5A-TST_ANA-PadD5)") (class "Default")
      (node (ref "U5") (pin "D5") (pinfunction "TST_ANA_D5") (pintype "output+no_connect"))
    )
    (net (code "83") (name "unconnected-(U5A-TXER0-PadC2)") (class "Default")
      (node (ref "U5") (pin "C2") (pinfunction "TXER0_C2") (pintype "input+no_connect"))
    )
    (net (code "84") (name "unconnected-(U5A-TXER1-PadJ2)") (class "Default")
      (node (ref "U5") (pin "J2") (pinfunction "TXER1_J2") (pintype "input+no_connect"))
    )
    (net (code "85") (name "unconnected-(U5A-VOUT-PadK10)") (class "Default")
      (node (ref "U5") (pin "K10") (pinfunction "VOUT_K10") (pintype "power_in+no_connect"))
    )
    (net (code "86") (name "unconnected-(U5A-VOUT_FB-PadK11)") (class "Default")
      (node (ref "U5") (pin "K11") (pinfunction "VOUT_FB_K11") (pintype "input+no_connect"))
    )
    (net (code "87") (name "unconnected-(U5B-MFCIO04-PadH8)") (class "Default")
      (node (ref "U5") (pin "H8") (pinfunction "MFCIO04_H8") (pintype "bidirectional+no_connect"))
    )
    (net (code "88") (name "unconnected-(U5B-MFCIO05-PadH9)") (class "Default")
      (node (ref "U5") (pin "H9") (pinfunction "MFCIO05_H9") (pintype "bidirectional+no_connect"))
    )
    (net (code "89") (name "unconnected-(U5B-MFCIO06-PadH10)") (class "Default")
      (node (ref "U5") (pin "H10") (pinfunction "MFCIO06_H10") (pintype "bidirectional+no_connect"))
    )
    (net (code "90") (name "unconnected-(U5B-MFCIO07-PadH11)") (class "Default")
      (node (ref "U5") (pin "H11") (pinfunction "MFCIO07_H11") (pintype "bidirectional+no_connect"))
    )
    (net (code "91") (name "unconnected-(U5B-MFCIO08-PadD8)") (class "Default")
      (node (ref "U5") (pin "D8") (pinfunction "MFCIO08_D8") (pintype "bidirectional+no_connect"))
    )
    (net (code "92") (name "unconnected-(U5B-MFCIO09-PadD9)") (class "Default")
      (node (ref "U5") (pin "D9") (pinfunction "MFCIO09_D9") (pintype "bidirectional+no_connect"))
    )
    (net (code "93") (name "unconnected-(U5B-MFCIO10-PadD10)") (class "Default")
      (node (ref "U5") (pin "D10") (pinfunction "MFCIO10_D10") (pintype "bidirectional+no_connect"))
    )
    (net (code "94") (name "unconnected-(U5B-MFCIO11-PadD11)") (class "Default")
      (node (ref "U5") (pin "D11") (pinfunction "MFCIO11_D11") (pintype "bidirectional+no_connect"))
    )
    (net (code "95") (name "unconnected-(U5B-MFCIO12-PadC8)") (class "Default")
      (node (ref "U5") (pin "C8") (pinfunction "MFCIO12_C8") (pintype "bidirectional+no_connect"))
    )
    (net (code "96") (name "unconnected-(U5B-MFCIO13-PadC9)") (class "Default")
      (node (ref "U5") (pin "C9") (pinfunction "MFCIO13_C9") (pintype "bidirectional+no_connect"))
    )
    (net (code "97") (name "unconnected-(U5B-MFCIO14-PadC10)") (class "Default")
      (node (ref "U5") (pin "C10") (pinfunction "MFCIO14_C10") (pintype "bidirectional+no_connect"))
    )
    (net (code "98") (name "unconnected-(U5B-MFCIO15-PadC11)") (class "Default")
      (node (ref "U5") (pin "C11") (pinfunction "MFCIO15_C11") (pintype "bidirectional+no_connect"))
    )
    (net (code "99") (name "unconnected-(U5B-RXCLK0-PadD2)") (class "Default")
      (node (ref "U5") (pin "D2") (pinfunction "RXCLK0_D2") (pintype "bidirectional+no_connect"))
    )
    (net (code "100") (name "unconnected-(U5B-RXCLK1-PadG2)") (class "Default")
      (node (ref "U5") (pin "G2") (pinfunction "RXCLK1_G2") (pintype "bidirectional+no_connect"))
    )
    (net (code "101") (name "unconnected-(U5B-TXCLK0-PadE2)") (class "Default")
      (node (ref "U5") (pin "E2") (pinfunction "TXCLK0_E2") (pintype "bidirectional+no_connect"))
    )
    (net (code "102") (name "unconnected-(U5B-TXCLK1-PadH2)") (class "Default")
      (node (ref "U5") (pin "H2") (pinfunction "TXCLK1_H2") (pintype "bidirectional+no_connect"))
    )
    (net (code "103") (name "unconnected-(U5B-VIO1-PadB5)") (class "Default")
      (node (ref "U5") (pin "B5") (pinfunction "VIO1_B5") (pintype "power_in+no_connect"))
    )
    (net (code "104") (name "unconnected-(U5B-VIO2-PadB7)") (class "Default")
      (node (ref "U5") (pin "B7") (pinfunction "VIO2_B7") (pintype "power_in+no_connect"))
    )
    (net (code "105") (name "unconnected-(U5B-VIO3-PadB9)") (class "Default")
      (node (ref "U5") (pin "B9") (pinfunction "VIO3_B9") (pintype "power_in+no_connect"))
    )
    (net (code "106") (name "unconnected-(U5B-VS0-PadL7)") (class "Default")
      (node (ref "U5") (pin "L7") (pinfunction "VS0_L7") (pintype "power_in+no_connect"))
    )
    (net (code "107") (name "unconnected-(U5B-VS1-PadL11)") (class "Default")
      (node (ref "U5") (pin "L11") (pinfunction "VS1_L11") (pintype "input+no_connect"))
    )
    (net (code "108") (name "unconnected-(X1-OE{slash}~{ST}{slash}NC-Pad1)") (class "Default")
      (node (ref "X1") (pin "1") (pinfunction "OE/~{ST}/NC_1") (pintype "passive"))
    )
  )
)
